# rclights.net
KiCad netlist of a schematic drawn in EAGLE
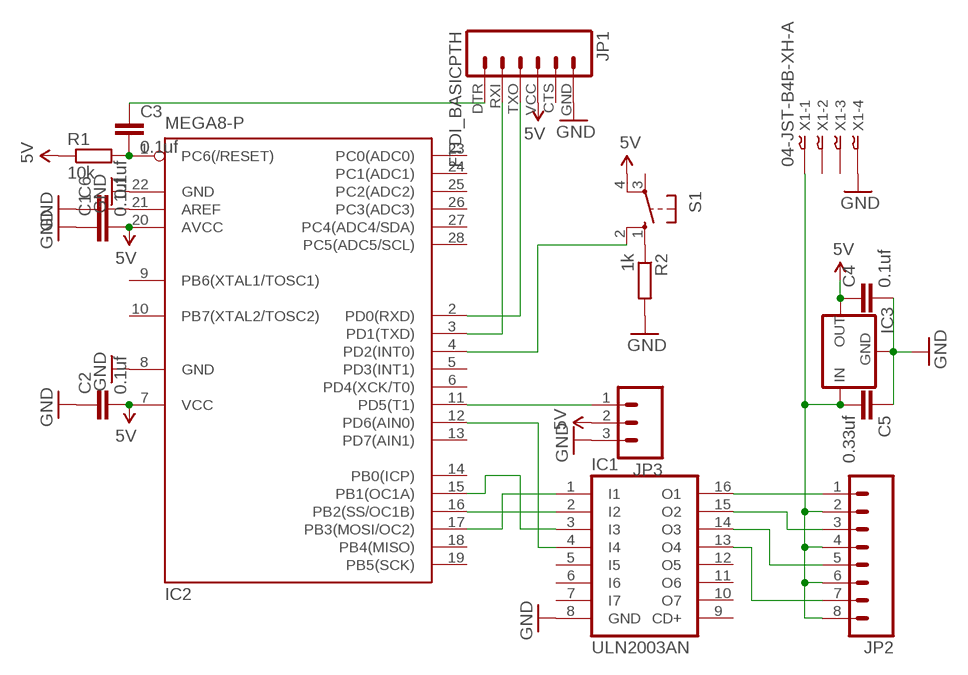
[diagram p0: schematic, sheet 1]

(export (version "E")
  (design (tool "Eeschema 10.0.6"))
  (components
    (comp (ref "C1")
      (value "0.1uf")
      (footprint "eagle-import:C025-025X050")
      (libsource (lib "eagle-import") (part "C-EU025-025X050"))
    )
    (comp (ref "C2")
      (value "0.1uf")
      (footprint "eagle-import:C025-025X050")
      (libsource (lib "eagle-import") (part "C-EU025-025X050"))
    )
    (comp (ref "C3")
      (value "0.1uf")
      (footprint "eagle-import:C025-025X050")
      (libsource (lib "eagle-import") (part "C-EU025-025X050"))
    )
    (comp (ref "C4")
      (value "0.1uf")
      (footprint "eagle-import:C025-025X050")
      (libsource (lib "eagle-import") (part "C-EU025-025X050"))
    )
    (comp (ref "C5")
      (value "0.33uf")
      (footprint "eagle-import:C025-025X050")
      (libsource (lib "eagle-import") (part "C-EU025-025X050"))
    )
    (comp (ref "C6")
      (value "0.1uf")
      (footprint "eagle-import:C025-025X050")
      (libsource (lib "eagle-import") (part "C-EU025-025X050"))
    )
    (comp (ref "IC1")
      (value "ULN2003AN")
      (footprint "eagle-import:DIL16")
      (libsource (lib "eagle-import") (part "ULN2003AN"))
    )
    (comp (ref "IC2")
      (value "MEGA8-P")
      (footprint "eagle-import:DIL28-3")
      (libsource (lib "eagle-import") (part "MEGA8-P"))
    )
    (comp (ref "IC3")
      (value "V_REG_78XX-TO-220")
      (footprint "eagle-import:TO-220-ALT")
      (libsource (lib "eagle-import") (part "V_REG_78XX-TO-220"))
    )
    (comp (ref "JP1")
      (value "FTDI_BASICPTH")
      (footprint "eagle-import:FTDI_BASIC")
      (libsource (lib "eagle-import") (part "FTDI_BASICPTH"))
    )
    (comp (ref "JP2")
      (value "M081X08")
      (footprint "eagle-import:1X08")
      (libsource (lib "eagle-import") (part "M081X08"))
    )
    (comp (ref "JP3")
      (value "M03PTH")
      (footprint "eagle-import:1X03")
      (libsource (lib "eagle-import") (part "M03PTH"))
    )
    (comp (ref "R1")
      (value "10k")
      (footprint "eagle-import:0207_10")
      (libsource (lib "eagle-import") (part "R-EU_0207/10"))
    )
    (comp (ref "R2")
      (value "1k")
      (footprint "eagle-import:0207_10")
      (libsource (lib "eagle-import") (part "R-EU_0207/10"))
    )
    (comp (ref "S1")
      (value "10-XX")
      (footprint "eagle-import:B3F-10XX")
      (fields (field (name "MPN") "B3F-1000"))
      (libsource (lib "eagle-import") (part "10-XX"))
    )
    (comp (ref "X1")
      (value "04-JST-B4B-XH-A")
      (footprint "eagle-import:B4B-XH")
      (libsource (lib "eagle-import") (part "04-JST-B4B-XH-A"))
    )
  )
  (nets
    (net (code "1") (name "5V") (class "Default")
      (node (ref "C1") (pin "2") (pinfunction "2_2") (pintype "passive"))
      (node (ref "C2") (pin "2") (pinfunction "2_2") (pintype "passive"))
      (node (ref "C4") (pin "1") (pinfunction "1_1") (pintype "passive"))
      (node (ref "IC2") (pin "20") (pinfunction "AVCC_20") (pintype "power_in"))
      (node (ref "IC2") (pin "7") (pinfunction "VCC_7") (pintype "power_in"))
      (node (ref "IC3") (pin "OUT") (pinfunction "OUT_OUT") (pintype "output"))
      (node (ref "JP1") (pin "VCC") (pinfunction "4_VCC") (pintype "passive"))
      (node (ref "JP3") (pin "2") (pinfunction "2_2") (pintype "passive"))
      (node (ref "R1") (pin "1") (pinfunction "1_1") (pintype "passive"))
      (node (ref "S1") (pin "4") (pinfunction "P1_4") (pintype "passive"))
    )
    (net (code "2") (name "GND") (class "Default")
      (node (ref "C1") (pin "1") (pinfunction "1_1") (pintype "passive"))
      (node (ref "C2") (pin "1") (pinfunction "1_1") (pintype "passive"))
      (node (ref "C4") (pin "2") (pinfunction "2_2") (pintype "passive"))
      (node (ref "C5") (pin "1") (pinfunction "1_1") (pintype "passive"))
      (node (ref "C6") (pin "1") (pinfunction "1_1") (pintype "passive"))
      (node (ref "IC1") (pin "8") (pinfunction "GND_8") (pintype "power_in"))
      (node (ref "IC2") (pin "22") (pinfunction "GND_22") (pintype "power_in"))
      (node (ref "IC2") (pin "8") (pinfunction "GND_8") (pintype "power_in"))
      (node (ref "IC3") (pin "GND") (pinfunction "GND_GND") (pintype "input"))
      (node (ref "JP1") (pin "GND") (pinfunction "6_GND") (pintype "passive"))
      (node (ref "JP3") (pin "3") (pinfunction "3_3") (pintype "passive"))
      (node (ref "R2") (pin "2") (pinfunction "2_2") (pintype "passive"))
      (node (ref "X1") (pin "P$4") (pinfunction "1_P$4") (pintype "passive"))
    )
    (net (code "3") (name "Net-(IC1-I1)") (class "Default")
      (node (ref "IC1") (pin "1") (pinfunction "I1_1") (pintype "input"))
      (node (ref "IC2") (pin "17") (pinfunction "PB3(MOSI/OC2)_17") (pintype "bidirectional"))
    )
    (net (code "4") (name "Net-(IC1-I2)") (class "Default")
      (node (ref "IC1") (pin "2") (pinfunction "I2_2") (pintype "input"))
      (node (ref "IC2") (pin "16") (pinfunction "PB2(SS/OC1B)_16") (pintype "bidirectional"))
    )
    (net (code "5") (name "Net-(IC1-I3)") (class "Default")
      (node (ref "IC1") (pin "3") (pinfunction "I3_3") (pintype "input"))
      (node (ref "IC2") (pin "15") (pinfunction "PB1(OC1A)_15") (pintype "bidirectional"))
    )
    (net (code "6") (name "Net-(IC1-I4)") (class "Default")
      (node (ref "IC1") (pin "4") (pinfunction "I4_4") (pintype "input"))
      (node (ref "IC2") (pin "12") (pinfunction "PD6(AIN0)_12") (pintype "bidirectional"))
    )
    (net (code "7") (name "Net-(IC1-O1)") (class "Default")
      (node (ref "IC1") (pin "16") (pinfunction "O1_16") (pintype "open_collector"))
      (node (ref "JP2") (pin "1") (pinfunction "1_1") (pintype "passive"))
    )
    (net (code "8") (name "Net-(IC1-O2)") (class "Default")
      (node (ref "IC1") (pin "15") (pinfunction "O2_15") (pintype "open_collector"))
      (node (ref "JP2") (pin "3") (pinfunction "3_3") (pintype "passive"))
    )
    (net (code "9") (name "Net-(IC1-O3)") (class "Default")
      (node (ref "IC1") (pin "14") (pinfunction "O3_14") (pintype "open_collector"))
      (node (ref "JP2") (pin "5") (pinfunction "5_5") (pintype "passive"))
    )
    (net (code "10") (name "Net-(IC1-O4)") (class "Default")
      (node (ref "IC1") (pin "13") (pinfunction "O4_13") (pintype "open_collector"))
      (node (ref "JP2") (pin "7") (pinfunction "7_7") (pintype "passive"))
    )
    (net (code "11") (name "Net-(IC2-AREF)") (class "Default")
      (node (ref "C6") (pin "2") (pinfunction "2_2") (pintype "passive"))
      (node (ref "IC2") (pin "21") (pinfunction "AREF_21") (pintype "passive"))
    )
    (net (code "12") (name "Net-(IC2-PC6({slash}RESET))") (class "Default")
      (node (ref "C3") (pin "2") (pinfunction "2_2") (pintype "passive"))
      (node (ref "IC2") (pin "1") (pinfunction "PC6(/RESET)_1") (pintype "bidirectional"))
      (node (ref "R1") (pin "2") (pinfunction "2_2") (pintype "passive"))
    )
    (net (code "13") (name "Net-(IC2-PD0(RXD))") (class "Default")
      (node (ref "IC2") (pin "2") (pinfunction "PD0(RXD)_2") (pintype "bidirectional"))
      (node (ref "JP1") (pin "TXO") (pinfunction "3_TXO") (pintype "passive"))
    )
    (net (code "14") (name "Net-(IC2-PD1(TXD))") (class "Default")
      (node (ref "IC2") (pin "3") (pinfunction "PD1(TXD)_3") (pintype "bidirectional"))
      (node (ref "JP1") (pin "RXI") (pinfunction "2_RXI") (pintype "passive"))
    )
    (net (code "15") (name "Net-(IC2-PD2(INT0))") (class "Default")
      (node (ref "IC2") (pin "4") (pinfunction "PD2(INT0)_4") (pintype "bidirectional"))
      (node (ref "S1") (pin "2") (pinfunction "S1_2") (pintype "passive"))
    )
    (net (code "16") (name "Net-(IC2-PD5(T1))") (class "Default")
      (node (ref "IC2") (pin "11") (pinfunction "PD5(T1)_11") (pintype "bidirectional"))
      (node (ref "JP3") (pin "1") (pinfunction "1_1") (pintype "passive"))
    )
    (net (code "17") (name "Net-(JP1-1)") (class "Default")
      (node (ref "C3") (pin "1") (pinfunction "1_1") (pintype "passive"))
      (node (ref "JP1") (pin "DTR") (pinfunction "1_DTR") (pintype "passive"))
    )
    (net (code "18") (name "Net-(S1-S)") (class "Default")
      (node (ref "R2") (pin "1") (pinfunction "1_1") (pintype "passive"))
      (node (ref "S1") (pin "1") (pinfunction "S_1") (pintype "passive"))
    )
    (net (code "19") (name "Net-(X1A-1)") (class "Default")
      (node (ref "C5") (pin "2") (pinfunction "2_2") (pintype "passive"))
      (node (ref "IC3") (pin "IN") (pinfunction "IN_IN") (pintype "input"))
      (node (ref "JP2") (pin "2") (pinfunction "2_2") (pintype "passive"))
      (node (ref "JP2") (pin "4") (pinfunction "4_4") (pintype "passive"))
      (node (ref "JP2") (pin "6") (pinfunction "6_6") (pintype "passive"))
      (node (ref "JP2") (pin "8") (pinfunction "8_8") (pintype "passive"))
      (node (ref "X1") (pin "P$1") (pinfunction "1_P$1") (pintype "passive"))
    )
    (net (code "20") (name "unconnected-(IC1-CD+-Pad9)") (class "Default")
      (node (ref "IC1") (pin "9") (pinfunction "CD+_9") (pintype "passive"))
    )
    (net (code "21") (name "unconnected-(IC1-I5-Pad5)") (class "Default")
      (node (ref "IC1") (pin "5") (pinfunction "I5_5") (pintype "input"))
    )
    (net (code "22") (name "unconnected-(IC1-I6-Pad6)") (class "Default")
      (node (ref "IC1") (pin "6") (pinfunction "I6_6") (pintype "input"))
    )
    (net (code "23") (name "unconnected-(IC1-I7-Pad7)") (class "Default")
      (node (ref "IC1") (pin "7") (pinfunction "I7_7") (pintype "input"))
    )
    (net (code "24") (name "unconnected-(IC1-O5-Pad12)") (class "Default")
      (node (ref "IC1") (pin "12") (pinfunction "O5_12") (pintype "open_collector"))
    )
    (net (code "25") (name "unconnected-(IC1-O6-Pad11)") (class "Default")
      (node (ref "IC1") (pin "11") (pinfunction "O6_11") (pintype "open_collector"))
    )
    (net (code "26") (name "unconnected-(IC1-O7-Pad10)") (class "Default")
      (node (ref "IC1") (pin "10") (pinfunction "O7_10") (pintype "open_collector"))
    )
    (net (code "27") (name "unconnected-(IC2-PB0(ICP)-Pad14)") (class "Default")
      (node (ref "IC2") (pin "14") (pinfunction "PB0(ICP)_14") (pintype "bidirectional"))
    )
    (net (code "28") (name "unconnected-(IC2-PB4(MISO)-Pad18)") (class "Default")
      (node (ref "IC2") (pin "18") (pinfunction "PB4(MISO)_18") (pintype "bidirectional"))
    )
    (net (code "29") (name "unconnected-(IC2-PB5(SCK)-Pad19)") (class "Default")
      (node (ref "IC2") (pin "19") (pinfunction "PB5(SCK)_19") (pintype "bidirectional"))
    )
    (net (code "30") (name "unconnected-(IC2-PB6(XTAL1{slash}TOSC1)-Pad9)") (class "Default")
      (node (ref "IC2") (pin "9") (pinfunction "PB6(XTAL1/TOSC1)_9") (pintype "bidirectional"))
    )
    (net (code "31") (name "unconnected-(IC2-PB7(XTAL2{slash}TOSC2)-Pad10)") (class "Default")
      (node (ref "IC2") (pin "10") (pinfunction "PB7(XTAL2/TOSC2)_10") (pintype "bidirectional"))
    )
    (net (code "32") (name "unconnected-(IC2-PC0(ADC0)-Pad23)") (class "Default")
      (node (ref "IC2") (pin "23") (pinfunction "PC0(ADC0)_23") (pintype "bidirectional"))
    )
    (net (code "33") (name "unconnected-(IC2-PC1(ADC1)-Pad24)") (class "Default")
      (node (ref "IC2") (pin "24") (pinfunction "PC1(ADC1)_24") (pintype "bidirectional"))
    )
    (net (code "34") (name "unconnected-(IC2-PC2(ADC2)-Pad25)") (class "Default")
      (node (ref "IC2") (pin "25") (pinfunction "PC2(ADC2)_25") (pintype "bidirectional"))
    )
    (net (code "35") (name "unconnected-(IC2-PC3(ADC3)-Pad26)") (class "Default")
      (node (ref "IC2") (pin "26") (pinfunction "PC3(ADC3)_26") (pintype "bidirectional"))
    )
    (net (code "36") (name "unconnected-(IC2-PC4(ADC4{slash}SDA)-Pad27)") (class "Default")
      (node (ref "IC2") (pin "27") (pinfunction "PC4(ADC4/SDA)_27") (pintype "bidirectional"))
    )
    (net (code "37") (name "unconnected-(IC2-PC5(ADC5{slash}SCL)-Pad28)") (class "Default")
      (node (ref "IC2") (pin "28") (pinfunction "PC5(ADC5/SCL)_28") (pintype "bidirectional"))
    )
    (net (code "38") (name "unconnected-(IC2-PD3(INT1)-Pad5)") (class "Default")
      (node (ref "IC2") (pin "5") (pinfunction "PD3(INT1)_5") (pintype "bidirectional"))
    )
    (net (code "39") (name "unconnected-(IC2-PD4(XCK{slash}T0)-Pad6)") (class "Default")
      (node (ref "IC2") (pin "6") (pinfunction "PD4(XCK/T0)_6") (pintype "bidirectional"))
    )
    (net (code "40") (name "unconnected-(IC2-PD7(AIN1)-Pad13)") (class "Default")
      (node (ref "IC2") (pin "13") (pinfunction "PD7(AIN1)_13") (pintype "bidirectional"))
    )
    (net (code "41") (name "unconnected-(JP1-5-PadCTS)") (class "Default")
      (node (ref "JP1") (pin "CTS") (pinfunction "5_CTS") (pintype "passive"))
    )
    (net (code "42") (name "unconnected-(S1-P-Pad3)") (class "Default")
      (node (ref "S1") (pin "3") (pinfunction "P_3") (pintype "passive"))
    )
    (net (code "43") (name "unconnected-(X1B-1-PadP$2)") (class "Default")
      (node (ref "X1") (pin "P$2") (pinfunction "1_P$2") (pintype "passive"))
    )
    (net (code "44") (name "unconnected-(X1C-1-PadP$3)") (class "Default")
      (node (ref "X1") (pin "P$3") (pinfunction "1_P$3") (pintype "passive"))
    )
  )
)
